# schematic.net
KiCad netlist of a schematic drawn in Altium Designer
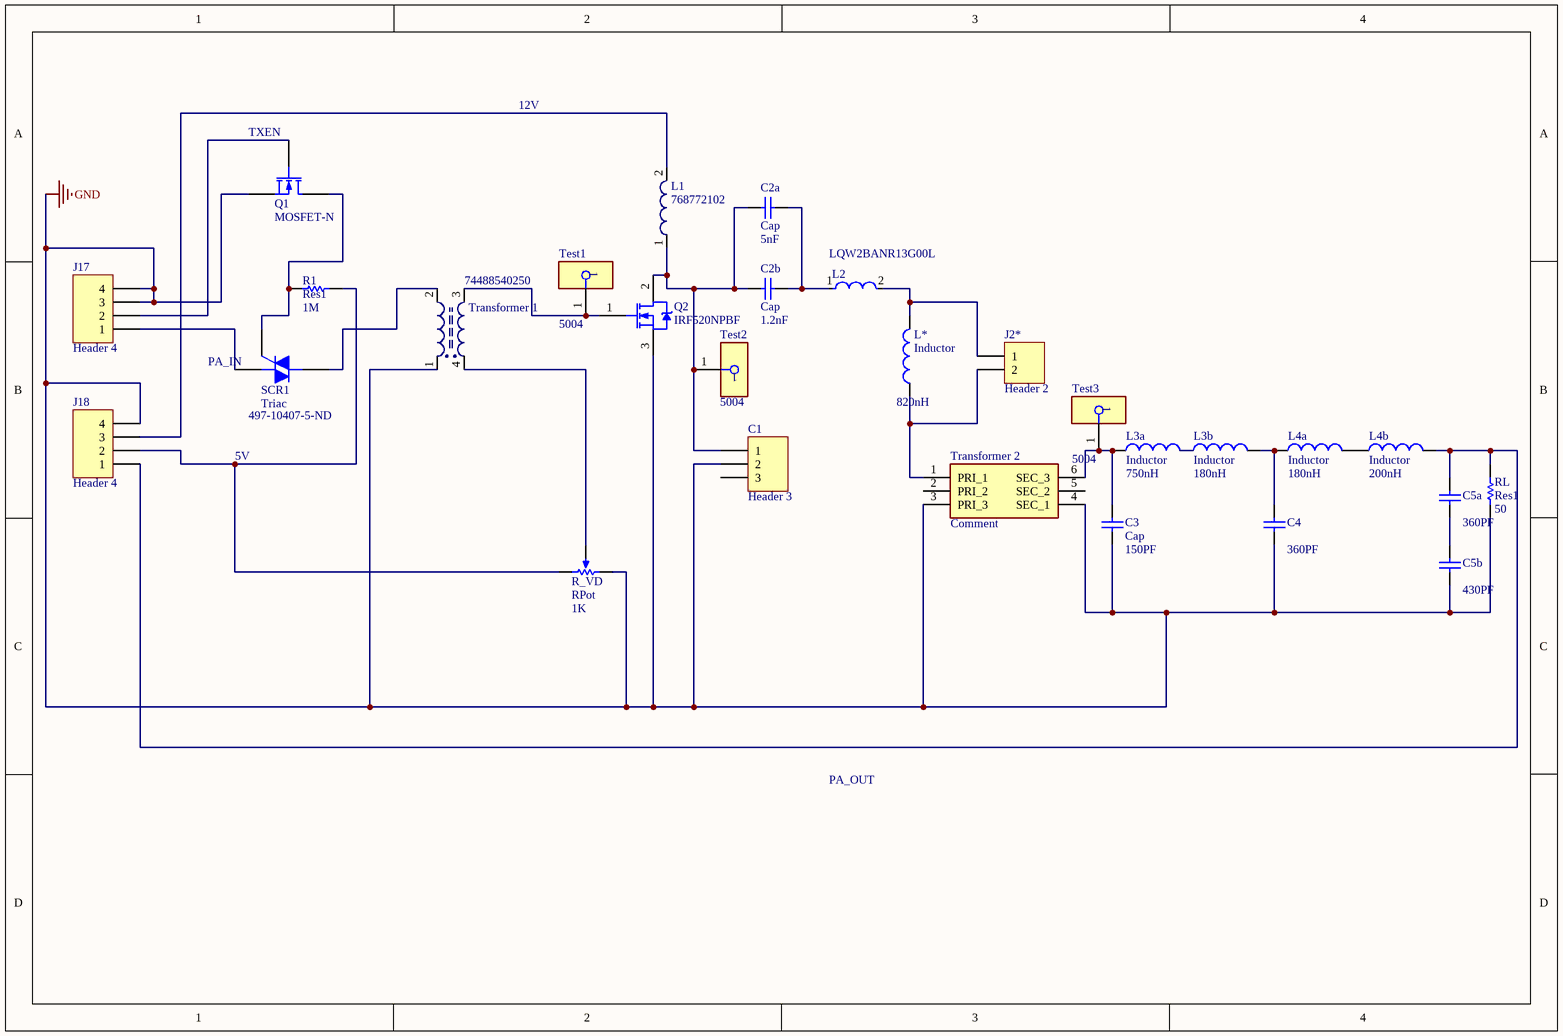
[diagram p0: schematic.SchDoc]

(export (version "E")
  (design (tool "Eeschema 10.0.6"))
  (components
    (comp (ref "C1")
      (value "Header 3")
      (footprint "Potentiometer")
      (description "Header, 3-Pin")
      (fields (field (name "PUBLISHER") "Altium Limited"))
      (libsource (lib "Miscellaneous Connectors") (part "Header 3"))
    )
    (comp (ref "C2a")
      (value "Cap")
      (footprint "RAD-0.1")
      (fields
        (field (name "MANUFACTURER PART NUMBER") "EEA-GA1H1R5H")
        (field (name "ALTIUM_VALUE") "5nF")
        (field (name "MANUFACTURER") "KEMET")
        (field (name "PUBLISHER") "Altium Limited")
      )
      (libsource (lib "ECE295-Capacitors-TH") (part "CAP ALUM 1.5UF 20% 50V RADIAL"))
    )
    (comp (ref "C2b")
      (value "Cap")
      (footprint "RAD-0.1")
      (fields
        (field (name "MANUFACTURER PART NUMBER") "EEA-GA1H1R5H")
        (field (name "ALTIUM_VALUE") "1.2nF")
        (field (name "MANUFACTURER") "KEMET")
        (field (name "PUBLISHER") "Altium Limited")
      )
      (libsource (lib "ECE295-Capacitors-TH") (part "CAP ALUM 1.5UF 20% 50V RADIAL"))
    )
    (comp (ref "C3")
      (value "Cap")
      (footprint "RAD-0.1")
      (fields
        (field (name "MANUFACTURER PART NUMBER") "EEA-GA1H1R5H")
        (field (name "ALTIUM_VALUE") "150PF")
        (field (name "MANUFACTURER") "KEMET")
        (field (name "PUBLISHER") "Altium Limited")
      )
      (libsource (lib "ECE295-Capacitors-TH") (part "CAP ALUM 1.5UF 20% 50V RADIAL"))
    )
    (comp (ref "C4")
      (value "360PF")
      (footprint "RAD-0.1")
      (description "Capacitor")
      (fields
        (field (name "MANUFACTURER PART NUMBER") "K331K15X7RF53L2")
        (field (name "Comment") "Cap")
        (field (name "PUBLISHER") "Altium Limited")
      )
      (libsource (lib "ECE295-Capacitors-TH") (part "CAP CER 330PF 50V X7R RADIAL"))
    )
    (comp (ref "C5a")
      (value "360PF")
      (footprint "RAD-0.1")
      (description "Capacitor")
      (fields
        (field (name "MANUFACTURER PART NUMBER") "K331K15X7RF53L2")
        (field (name "Comment") "Cap")
        (field (name "PUBLISHER") "Altium Limited")
      )
      (libsource (lib "ECE295-Capacitors-TH") (part "CAP CER 330PF 50V X7R RADIAL"))
    )
    (comp (ref "C5b")
      (value "430PF")
      (footprint "RAD-0.1")
      (description "Capacitor")
      (fields
        (field (name "MANUFACTURER PART NUMBER") "K331K15X7RF53L2")
        (field (name "Comment") "Cap")
        (field (name "PUBLISHER") "Altium Limited")
      )
      (libsource (lib "ECE295-Capacitors-TH") (part "CAP CER 330PF 50V X7R RADIAL"))
    )
    (comp (ref "J2*")
      (value "Header 2")
      (footprint "HDR1X2")
      (description "Header, 2-Pin")
      (fields (field (name "PUBLISHER") "Altium Limited"))
      (libsource (lib "Miscellaneous Connectors") (part "Header 2"))
    )
    (comp (ref "J17")
      (value "Header 4")
      (footprint "HDR1X4")
      (description "Header, 4-Pin")
      (fields (field (name "PUBLISHER") "Altium Limited"))
      (libsource (lib "Miscellaneous Connectors") (part "Header 4"))
    )
    (comp (ref "J18")
      (value "Header 4")
      (footprint "HDR1X4")
      (description "Header, 4-Pin")
      (fields (field (name "PUBLISHER") "Altium Limited"))
      (libsource (lib "Miscellaneous Connectors") (part "Header 4"))
    )
    (comp (ref "L*")
      (value "Inductor")
      (footprint "2029")
      (fields (field (name "ALTIUM_VALUE") "820nH") (field (name "PUBLISHER") "Altium Limited"))
      (libsource (lib "Miscellaneous Devices") (part "Inductor"))
    )
    (comp (ref "L1")
      (value "768772102")
      (footprint "8095")
      (description "SMD-Radial Leaded Wire Wound  Inductor WE-TI HV, L=1000 µH")
      (fields (field (name "MANUFACTURER") "Wuerth Elektronik"))
      (libsource (lib "Altium Content Vault") (part "WE-IND-INDUCTOR-2"))
    )
    (comp (ref "L2")
      (value "LQW2BANR13G00L")
      (footprint "FP-LQW2BAN_00-MFG")
      (description "Wire Wound RF Inductor 130nH ±2% 950mA 0.42Ω 0805 (2015)")
      (fields (field (name "TOLERANCE") "2%"))
      (libsource (lib "Altium Content Vault") (part "725321dda6339637d4d059423bc1c3c"))
    )
    (comp (ref "L3a")
      (value "Inductor")
      (footprint "2029")
      (fields (field (name "ALTIUM_VALUE") "750nH") (field (name "PUBLISHER") "Altium Limited"))
      (libsource (lib "Miscellaneous Devices") (part "Inductor"))
    )
    (comp (ref "L3b")
      (value "Inductor")
      (footprint "2029")
      (fields (field (name "ALTIUM_VALUE") "180nH") (field (name "PUBLISHER") "Altium Limited"))
      (libsource (lib "Miscellaneous Devices") (part "Inductor"))
    )
    (comp (ref "L4a")
      (value "Inductor")
      (footprint "2029")
      (fields (field (name "ALTIUM_VALUE") "180nH") (field (name "PUBLISHER") "Altium Limited"))
      (libsource (lib "Miscellaneous Devices") (part "Inductor"))
    )
    (comp (ref "L4b")
      (value "Inductor")
      (footprint "2029")
      (fields (field (name "ALTIUM_VALUE") "200nH") (field (name "PUBLISHER") "Altium Limited"))
      (libsource (lib "Miscellaneous Devices") (part "Inductor"))
    )
    (comp (ref "Q1")
      (value "MOSFET-N")
      (footprint "Transistor")
      (description "N-Channel MOSFET")
      (fields (field (name "PUBLISHER") "Altium Limited"))
      (libsource (lib "Miscellaneous Devices") (part "MOSFET-N"))
    )
    (comp (ref "Q2")
      (value "IRF520NPBF")
      (footprint "INTR-TO-220AB-3")
      (description "HEXFET(R) Power MOSFET, 100 V, 9.7 A, 0.2 Ohm, -55 to 175 degC, 3-Pin FM (TO-220AB), RoHS, Tube")
      (fields (field (name "MANUFACTURER") "International Rectifier"))
      (libsource (lib "Altium Content Vault") (part "NEMOS-GDS-3_B"))
    )
    (comp (ref "R1")
      (value "Res1")
      (footprint "AXIAL-0.4")
      (description "Resistor")
      (fields
        (field (name "ALTIUM_VALUE") "1M")
        (field (name "MANUFACTURER PART NUMBER") "CFR-25JB-52-150R")
        (field (name "TOLERANCE") "0.05")
        (field (name "PUBLISHER") "Altium Limited")
      )
      (libsource (lib "ECE295-Resistors-TH") (part "RES 150 OHM 5% 1/4W AXIAL"))
    )
    (comp (ref "RL")
      (value "Res1")
      (footprint "AXIAL-0.4")
      (description "Resistor")
      (fields
        (field (name "ALTIUM_VALUE") "50")
        (field (name "MANUFACTURER PART NUMBER") "CFR-25JB-52-150R")
        (field (name "TOLERANCE") "0.05")
        (field (name "PUBLISHER") "Altium Limited")
      )
      (libsource (lib "ECE295-Resistors-TH") (part "RES 150 OHM 5% 1/4W AXIAL"))
    )
    (comp (ref "R_VD")
      (value "RPot")
      (footprint "VR5")
      (description "Potentiometer")
      (fields (field (name "ALTIUM_VALUE") "1K") (field (name "PUBLISHER") "Altium Limited"))
      (libsource (lib "Miscellaneous Devices") (part "RPot"))
    )
    (comp (ref "SCR1")
      (value "Triac")
      (footprint "369-03")
      (description "Silicon Bidirectional Triode Thyristor")
      (fields
        (field (name "SUPPLIER PART NUMBER 1") "497-10407-5-ND")
        (field (name "PUBLISHER") "Altium Limited")
      )
      (libsource (lib "Miscellaneous Devices") (part "Triac"))
    )
    (comp (ref "Test1")
      (value "5004")
      (footprint "FP-5004-MFG")
      (description "PC TEST POINT MINIATURE YELLOW")
      (fields
        (field (name "MANUFACTURER") "Keystone")
        (field (name "OCTOPART") "https://octopart.com/5004-keystone-28591")
      )
      (libsource (lib "Altium Content Vault") (part "98815daf2f2c152b0c43f5ab9800df6"))
    )
    (comp (ref "Test2")
      (value "5004")
      (footprint "FP-5004-MFG")
      (description "PC TEST POINT MINIATURE YELLOW")
      (fields
        (field (name "MANUFACTURER") "Keystone")
        (field (name "OCTOPART") "https://octopart.com/5004-keystone-28591")
      )
      (libsource (lib "") (part "98815daf2f2c152b0c43f5ab9800df6_1"))
    )
    (comp (ref "Test3")
      (value "5004")
      (footprint "FP-5004-MFG")
      (description "PC TEST POINT MINIATURE YELLOW")
      (fields
        (field (name "MANUFACTURER") "Keystone")
        (field (name "OCTOPART") "https://octopart.com/5004-keystone-28591")
      )
      (libsource (lib "Altium Content Vault") (part "98815daf2f2c152b0c43f5ab9800df6"))
    )
    (comp (ref "Transformer 1")
      (value "74488540250")
      (footprint "WE-EHPI 5838")
      (description "Energy Harvesting Coupled Inductor,SMD, WE-EHPI, L=25.0 µH")
      (fields (field (name "MANUFACTURER") "Wuerth Elektronik"))
      (libsource (lib "Altium Content Vault") (part "WE-IND-INDUCTOR-4C"))
    )
    (comp (ref "Transformer 2")
      (value "Comment")
      (footprint "78931812515")
      (description "WE-PSPA Push Pull & Gate Drive Transformer NEW")
      (fields (field (name "MANUFACTURER_PART_NUMBER") "78931812515"))
      (libsource (lib "78931812515") (part "78931812515"))
    )
  )
  (nets
    (net (code "1") (name "GND") (class "Default")
      (node (ref "C1") (pin "2") (pinfunction "2_2") (pintype "passive"))
      (node (ref "C3") (pin "1") (pinfunction "1_1") (pintype "passive"))
      (node (ref "C4") (pin "1") (pinfunction "1_1") (pintype "passive"))
      (node (ref "C5b") (pin "1") (pinfunction "1_1") (pintype "passive"))
      (node (ref "J17") (pin "3") (pinfunction "3_3") (pintype "passive"))
      (node (ref "J17") (pin "4") (pinfunction "4_4") (pintype "passive"))
      (node (ref "J18") (pin "4") (pinfunction "4_4") (pintype "passive"))
      (node (ref "Q1") (pin "3") (pinfunction "S_3") (pintype "passive"))
      (node (ref "Q2") (pin "3") (pinfunction "S_3") (pintype "passive"))
      (node (ref "RL") (pin "1") (pinfunction "1_1") (pintype "passive"))
      (node (ref "R_VD") (pin "1") (pinfunction "TOP_1") (pintype "passive"))
      (node (ref "Transformer 1") (pin "1") (pinfunction "1_1") (pintype "passive"))
      (node (ref "Transformer 2") (pin "3") (pinfunction "PRI_3_3") (pintype "passive"))
      (node (ref "Transformer 2") (pin "4") (pinfunction "SEC_1_4") (pintype "passive"))
    )
    (net (code "2") (name "Net-(C2a-Pad2)") (class "Default")
      (node (ref "C2a") (pin "2") (pinfunction "2_2") (pintype "passive"))
      (node (ref "C2b") (pin "2") (pinfunction "2_2") (pintype "passive"))
      (node (ref "L2") (pin "1") (pinfunction "1_1") (pintype "passive"))
    )
    (net (code "3") (name "Net-(C4-Pad2)") (class "Default")
      (node (ref "C4") (pin "2") (pinfunction "2_2") (pintype "passive"))
      (node (ref "L3b") (pin "2") (pinfunction "2_2") (pintype "passive"))
      (node (ref "L4a") (pin "1") (pinfunction "1_1") (pintype "passive"))
    )
    (net (code "4") (name "Net-(C5a-Pad1)") (class "Default")
      (node (ref "C5a") (pin "1") (pinfunction "1_1") (pintype "passive"))
      (node (ref "C5b") (pin "2") (pinfunction "2_2") (pintype "passive"))
    )
    (net (code "5") (name "Net-(C5a-Pad2)") (class "Default")
      (node (ref "C5a") (pin "2") (pinfunction "2_2") (pintype "passive"))
      (node (ref "J18") (pin "1") (pinfunction "1_1") (pintype "passive"))
      (node (ref "L4b") (pin "2") (pinfunction "2_2") (pintype "passive"))
      (node (ref "RL") (pin "2") (pinfunction "2_2") (pintype "passive"))
    )
    (net (code "6") (name "Net-(J2*-Pad1)") (class "Default")
      (node (ref "J2*") (pin "1") (pinfunction "1_1") (pintype "passive"))
      (node (ref "L*") (pin "2") (pinfunction "2_2") (pintype "passive"))
      (node (ref "L2") (pin "2") (pinfunction "2_2") (pintype "passive"))
    )
    (net (code "7") (name "Net-(J18-Pad3)") (class "Default")
      (node (ref "J18") (pin "3") (pinfunction "3_3") (pintype "passive"))
      (node (ref "L1") (pin "2") (pinfunction "2_2") (pintype "passive"))
    )
    (net (code "8") (name "Net-(L3a-Pad2)") (class "Default")
      (node (ref "L3a") (pin "2") (pinfunction "2_2") (pintype "passive"))
      (node (ref "L3b") (pin "1") (pinfunction "1_1") (pintype "passive"))
    )
    (net (code "9") (name "Net-(L4a-Pad2)") (class "Default")
      (node (ref "L4a") (pin "2") (pinfunction "2_2") (pintype "passive"))
      (node (ref "L4b") (pin "1") (pinfunction "1_1") (pintype "passive"))
    )
    (net (code "10") (name "Net-(Q1-D)") (class "Default")
      (node (ref "Q1") (pin "1") (pinfunction "D_1") (pintype "passive"))
      (node (ref "R1") (pin "1") (pinfunction "1_1") (pintype "passive"))
      (node (ref "SCR1") (pin "3") (pinfunction "G_3") (pintype "passive"))
    )
    (net (code "11") (name "Net-(Q1-G)") (class "Default")
      (node (ref "J17") (pin "2") (pinfunction "2_2") (pintype "passive"))
      (node (ref "Q1") (pin "2") (pinfunction "G_2") (pintype "passive"))
    )
    (net (code "12") (name "Net-(Q2-D)") (class "Default")
      (node (ref "C1") (pin "1") (pinfunction "1_1") (pintype "passive"))
      (node (ref "C2a") (pin "1") (pinfunction "1_1") (pintype "passive"))
      (node (ref "C2b") (pin "1") (pinfunction "1_1") (pintype "passive"))
      (node (ref "L1") (pin "1") (pinfunction "1_1") (pintype "passive"))
      (node (ref "Q2") (pin "2") (pinfunction "D_2") (pintype "passive"))
      (node (ref "Test2") (pin "1") (pinfunction "1_1") (pintype "passive"))
    )
    (net (code "13") (name "Net-(Q2-G)") (class "Default")
      (node (ref "Q2") (pin "1") (pinfunction "G_1") (pintype "passive"))
      (node (ref "Test1") (pin "1") (pinfunction "1_1") (pintype "passive"))
      (node (ref "Transformer 1") (pin "3") (pinfunction "3_3") (pintype "passive"))
    )
    (net (code "14") (name "Net-(R_VD-BOT)") (class "Default")
      (node (ref "J18") (pin "2") (pinfunction "2_2") (pintype "passive"))
      (node (ref "R1") (pin "2") (pinfunction "2_2") (pintype "passive"))
      (node (ref "R_VD") (pin "2") (pinfunction "BOT_2") (pintype "passive"))
    )
    (net (code "15") (name "Net-(R_VD-TAP)") (class "Default")
      (node (ref "R_VD") (pin "3") (pinfunction "TAP_3") (pintype "passive"))
      (node (ref "Transformer 1") (pin "4") (pinfunction "4_4") (pintype "passive"))
    )
    (net (code "16") (name "Net-(SCR1-M1)") (class "Default")
      (node (ref "J17") (pin "1") (pinfunction "1_1") (pintype "passive"))
      (node (ref "SCR1") (pin "1") (pinfunction "M1_1") (pintype "passive"))
    )
    (net (code "17") (name "Net-(SCR1-M2)") (class "Default")
      (node (ref "SCR1") (pin "2") (pinfunction "M2_2") (pintype "passive"))
      (node (ref "Transformer 1") (pin "2") (pinfunction "2_2") (pintype "passive"))
    )
    (net (code "18") (name "Net-(Transformer 2-PRI_1)") (class "Default")
      (node (ref "J2*") (pin "2") (pinfunction "2_2") (pintype "passive"))
      (node (ref "L*") (pin "1") (pinfunction "1_1") (pintype "passive"))
      (node (ref "Transformer 2") (pin "1") (pinfunction "PRI_1_1") (pintype "passive"))
    )
    (net (code "19") (name "Net-(Transformer 2-SEC_3)") (class "Default")
      (node (ref "C3") (pin "2") (pinfunction "2_2") (pintype "passive"))
      (node (ref "L3a") (pin "1") (pinfunction "1_1") (pintype "passive"))
      (node (ref "Test3") (pin "1") (pinfunction "1_1") (pintype "passive"))
      (node (ref "Transformer 2") (pin "6") (pinfunction "SEC_3_6") (pintype "passive"))
    )
    (net (code "20") (name "unconnected-(C1-Pad3)") (class "Default")
      (node (ref "C1") (pin "3") (pinfunction "3_3") (pintype "passive"))
    )
    (net (code "21") (name "unconnected-(Transformer 2-PRI_2-Pad2)") (class "Default")
      (node (ref "Transformer 2") (pin "2") (pinfunction "PRI_2_2") (pintype "passive"))
    )
    (net (code "22") (name "unconnected-(Transformer 2-SEC_2-Pad5)") (class "Default")
      (node (ref "Transformer 2") (pin "5") (pinfunction "SEC_2_5") (pintype "passive"))
    )
  )
)
